# XC4216_DC_DC3_3V.net
KiCad netlist of a schematic drawn in Altium Designer
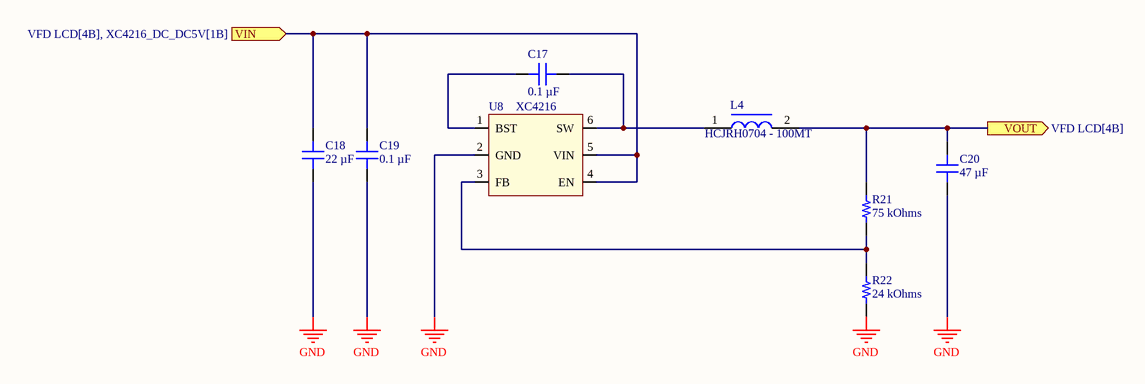
[diagram p0: XC4216_DC_DC3.3V.SchDoc]

(export (version "E")
  (design (tool "Eeschema 10.0.6"))
  (components
    (comp (ref "C17")
      (value "0.1 µF")
      (footprint "CAP 0805_2012")
      (description "CAP CER 0.1UF 50V X7R 0805")
      (fields (field (name "PART NUMBER") "CC0805MRX7R9BB104") (field (name "MANUFACTURER") "Yageo"))
      (libsource (lib "Celestial Altium Library - altium_library") (part "Capacitor"))
    )
    (comp (ref "C18")
      (value "22 µF")
      (footprint "CAP 0805_2012")
      (description "CAP CER 22UF 6.3V X6S 0805")
      (fields
        (field (name "PART NUMBER") "C2012X6S0J226M125AB")
        (field (name "MANUFACTURER") "TDK Corporation")
      )
      (libsource (lib "Celestial Altium Library - altium_library") (part "Capacitor"))
    )
    (comp (ref "C19")
      (value "0.1 µF")
      (footprint "CAP 0805_2012")
      (description "CAP CER 0.1UF 50V X7R 0805")
      (fields (field (name "PART NUMBER") "CC0805MRX7R9BB104") (field (name "MANUFACTURER") "Yageo"))
      (libsource (lib "Celestial Altium Library - altium_library") (part "Capacitor"))
    )
    (comp (ref "C20")
      (value "47 µF")
      (footprint "CAP 0805_2012")
      (description "CAP CER 47UF 4V X5R 0805")
      (fields (field (name "PART NUMBER") "AMK212BBJ476MD-T") (field (name "MANUFACTURER") "Taiyo Yuden"))
      (libsource (lib "Celestial Altium Library - altium_library") (part "Capacitor"))
    )
    (comp (ref "L4")
      (value "HCJRH0704 - 100MT")
      (footprint "HCJRH0704 - 100MT")
      (description "Inductor 10UH")
      (libsource (lib "My altlib") (part "HCJRH0704 - 100MT"))
    )
    (comp (ref "R21")
      (value "75 kOhms")
      (footprint "RES 0805_2012")
      (description "RES 75K OHM 1% 1/8W 0805")
      (fields
        (field (name "PART NUMBER") "RMCF0805FT75K0")
        (field (name "MANUFACTURER") "Stackpole Electronics Inc")
      )
      (libsource (lib "Celestial Altium Library - altium_library") (part "Resistor"))
    )
    (comp (ref "R22")
      (value "24 kOhms")
      (footprint "RES 0805_2012")
      (description "RES 24K OHM 0.1% 1/8W 0805")
      (fields (field (name "PART NUMBER") "TNPW080524K0BEEA") (field (name "MANUFACTURER") "Vishay Dale"))
      (libsource (lib "Celestial Altium Library - altium_library") (part "Resistor"))
    )
    (comp (ref "U8") (value "XC4216") (footprint "SOT-23-6") (libsource (lib "My altlib") (part "XC4216")))
  )
  (nets
    (net (code "1") (name "/VIN") (class "Default")
      (node (ref "C18") (pin "2") (pinfunction "2_2") (pintype "passive"))
      (node (ref "C19") (pin "2") (pinfunction "2_2") (pintype "passive"))
      (node (ref "U8") (pin "4") (pinfunction "EN_4") (pintype "passive"))
      (node (ref "U8") (pin "5") (pinfunction "VIN_5") (pintype "passive"))
    )
    (net (code "2") (name "/VOUT") (class "Default")
      (node (ref "C20") (pin "2") (pinfunction "2_2") (pintype "passive"))
      (node (ref "L4") (pin "2") (pinfunction "6_2") (pintype "passive"))
      (node (ref "R21") (pin "2") (pinfunction "2_2") (pintype "passive"))
    )
    (net (code "3") (name "GND") (class "Default")
      (node (ref "C18") (pin "1") (pinfunction "1_1") (pintype "passive"))
      (node (ref "C19") (pin "1") (pinfunction "1_1") (pintype "passive"))
      (node (ref "C20") (pin "1") (pinfunction "1_1") (pintype "passive"))
      (node (ref "R22") (pin "1") (pinfunction "1_1") (pintype "passive"))
      (node (ref "U8") (pin "2") (pinfunction "GND_2") (pintype "passive"))
    )
    (net (code "4") (name "Net-(U8-BST)") (class "Default")
      (node (ref "C17") (pin "1") (pinfunction "1_1") (pintype "passive"))
      (node (ref "U8") (pin "1") (pinfunction "BST_1") (pintype "passive"))
    )
    (net (code "5") (name "Net-(U8-FB)") (class "Default")
      (node (ref "R21") (pin "1") (pinfunction "1_1") (pintype "passive"))
      (node (ref "R22") (pin "2") (pinfunction "2_2") (pintype "passive"))
      (node (ref "U8") (pin "3") (pinfunction "FB_3") (pintype "passive"))
    )
    (net (code "6") (name "Net-(U8-SW)") (class "Default")
      (node (ref "C17") (pin "2") (pinfunction "2_2") (pintype "passive"))
      (node (ref "L4") (pin "1") (pinfunction "6_1") (pintype "passive"))
      (node (ref "U8") (pin "6") (pinfunction "SW_6") (pintype "passive"))
    )
  )
)
